# power_board.net
KiCad netlist of a schematic drawn in EAGLE
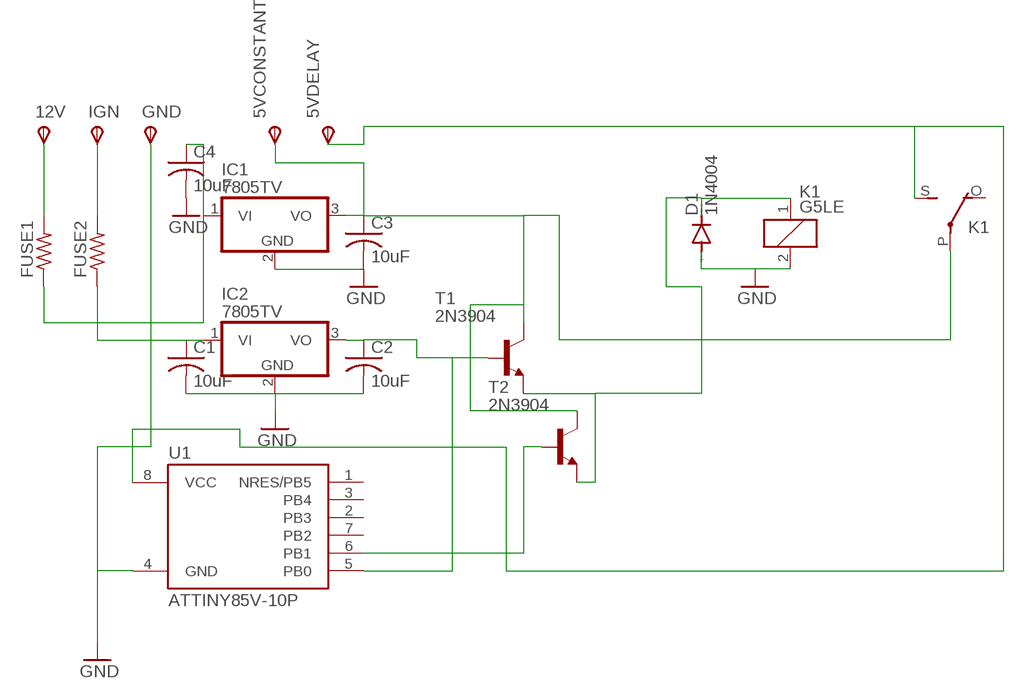
[diagram p0: schematic, sheet 1]

(export (version "E")
  (design (tool "Eeschema 10.0.6"))
  (components
    (comp (ref "5VCONSTANT")
      (value "TPSPAD1-13Y")
      (footprint "eagle-import:P1-13Y")
      (libsource (lib "eagle-import") (part "TPSPAD1-13Y"))
    )
    (comp (ref "5VDELAY")
      (value "TPSPAD1-13Y")
      (footprint "eagle-import:P1-13Y")
      (libsource (lib "eagle-import") (part "TPSPAD1-13Y"))
    )
    (comp (ref "12V")
      (value "TPSPAD1-13Y")
      (footprint "eagle-import:P1-13Y")
      (libsource (lib "eagle-import") (part "TPSPAD1-13Y"))
    )
    (comp (ref "C1")
      (value "10uF")
      (footprint "eagle-import:C0603")
      (libsource (lib "eagle-import") (part "C-USC0603"))
    )
    (comp (ref "C2")
      (value "10uF")
      (footprint "eagle-import:C0603")
      (libsource (lib "eagle-import") (part "C-USC0603"))
    )
    (comp (ref "C3")
      (value "10uF")
      (footprint "eagle-import:C0603")
      (libsource (lib "eagle-import") (part "C-USC0603"))
    )
    (comp (ref "C4")
      (value "10uF")
      (footprint "eagle-import:C0603")
      (libsource (lib "eagle-import") (part "C-USC0603"))
    )
    (comp (ref "D1")
      (value "1N4004")
      (footprint "eagle-import:DO41-10")
      (libsource (lib "eagle-import") (part "1N4004"))
    )
    (comp (ref "FUSE1")
      (value "R-US_R0805")
      (footprint "eagle-import:R0805")
      (libsource (lib "eagle-import") (part "R-US_R0805"))
    )
    (comp (ref "FUSE2")
      (value "R-US_R0805")
      (footprint "eagle-import:R0805")
      (libsource (lib "eagle-import") (part "R-US_R0805"))
    )
    (comp (ref "GND")
      (value "TPSPAD1-13Y")
      (footprint "eagle-import:P1-13Y")
      (libsource (lib "eagle-import") (part "TPSPAD1-13Y"))
    )
    (comp (ref "IC1")
      (value "7805TV")
      (footprint "eagle-import:TO220V")
      (libsource (lib "eagle-import") (part "78TV05"))
    )
    (comp (ref "IC2")
      (value "7805TV")
      (footprint "eagle-import:TO220V")
      (libsource (lib "eagle-import") (part "78TV05"))
    )
    (comp (ref "IGN")
      (value "TPSPAD1-13Y")
      (footprint "eagle-import:P1-13Y")
      (libsource (lib "eagle-import") (part "TPSPAD1-13Y"))
    )
    (comp (ref "K1")
      (value "G5LE")
      (footprint "eagle-import:G5LE")
      (libsource (lib "eagle-import") (part "G5LE"))
    )
    (comp (ref "T1")
      (value "2N3904")
      (footprint "eagle-import:TO92")
      (libsource (lib "eagle-import") (part "2N3904"))
    )
    (comp (ref "T2")
      (value "2N3904")
      (footprint "eagle-import:TO92")
      (libsource (lib "eagle-import") (part "2N3904"))
    )
    (comp (ref "U1")
      (value "ATTINY85V-10P")
      (footprint "eagle-import:PDIP08_300MIL")
      (libsource (lib "eagle-import") (part "ATTINY85PV-10"))
    )
  )
  (nets
    (net (code "1") (name "GND") (class "Default")
      (node (ref "C1") (pin "2") (pinfunction "2_2") (pintype "passive"))
      (node (ref "C2") (pin "2") (pinfunction "2_2") (pintype "passive"))
      (node (ref "C3") (pin "2") (pinfunction "2_2") (pintype "passive"))
      (node (ref "C4") (pin "2") (pinfunction "2_2") (pintype "passive"))
      (node (ref "D1") (pin "A") (pinfunction "A_A") (pintype "passive"))
      (node (ref "GND") (pin "TP") (pinfunction "PP_TP") (pintype "input"))
      (node (ref "IC1") (pin "2") (pinfunction "GND_2") (pintype "passive"))
      (node (ref "IC2") (pin "2") (pinfunction "GND_2") (pintype "passive"))
      (node (ref "K1") (pin "2") (pinfunction "2_2") (pintype "passive"))
      (node (ref "U1") (pin "4") (pinfunction "GND_4") (pintype "power_in"))
    )
    (net (code "2") (name "Net-(5VCONSTANT-PP)") (class "Default")
      (node (ref "5VCONSTANT") (pin "TP") (pinfunction "PP_TP") (pintype "input"))
      (node (ref "C3") (pin "1") (pinfunction "1_1") (pintype "passive"))
      (node (ref "IC1") (pin "3") (pinfunction "VO_3") (pintype "passive"))
      (node (ref "K1") (pin "P") (pinfunction "P_P") (pintype "passive"))
      (node (ref "T1") (pin "1") (pinfunction "C_1") (pintype "passive"))
      (node (ref "T2") (pin "1") (pinfunction "C_1") (pintype "passive"))
    )
    (net (code "3") (name "Net-(5VDELAY-PP)") (class "Default")
      (node (ref "5VDELAY") (pin "TP") (pinfunction "PP_TP") (pintype "input"))
      (node (ref "K1") (pin "S") (pinfunction "S_S") (pintype "passive"))
      (node (ref "U1") (pin "8") (pinfunction "VCC_8") (pintype "power_in"))
    )
    (net (code "4") (name "Net-(12V-PP)") (class "Default")
      (node (ref "12V") (pin "TP") (pinfunction "PP_TP") (pintype "input"))
      (node (ref "FUSE1") (pin "2") (pinfunction "2_2") (pintype "passive"))
    )
    (net (code "5") (name "Net-(IC1-VI)") (class "Default")
      (node (ref "C4") (pin "1") (pinfunction "1_1") (pintype "passive"))
      (node (ref "FUSE1") (pin "1") (pinfunction "1_1") (pintype "passive"))
      (node (ref "IC1") (pin "1") (pinfunction "VI_1") (pintype "input"))
    )
    (net (code "6") (name "Net-(IC2-VI)") (class "Default")
      (node (ref "C1") (pin "1") (pinfunction "1_1") (pintype "passive"))
      (node (ref "FUSE2") (pin "1") (pinfunction "1_1") (pintype "passive"))
      (node (ref "IC2") (pin "1") (pinfunction "VI_1") (pintype "input"))
    )
    (net (code "7") (name "Net-(IC2-VO)") (class "Default")
      (node (ref "C2") (pin "1") (pinfunction "1_1") (pintype "passive"))
      (node (ref "IC2") (pin "3") (pinfunction "VO_3") (pintype "passive"))
      (node (ref "T1") (pin "2") (pinfunction "B_2") (pintype "passive"))
      (node (ref "U1") (pin "5") (pinfunction "PB0_5") (pintype "bidirectional"))
    )
    (net (code "8") (name "Net-(IGN-PP)") (class "Default")
      (node (ref "FUSE2") (pin "2") (pinfunction "2_2") (pintype "passive"))
      (node (ref "IGN") (pin "TP") (pinfunction "PP_TP") (pintype "input"))
    )
    (net (code "9") (name "Net-(T1-E)") (class "Default")
      (node (ref "D1") (pin "C") (pinfunction "C_C") (pintype "passive"))
      (node (ref "K1") (pin "1") (pinfunction "1_1") (pintype "passive"))
      (node (ref "T1") (pin "3") (pinfunction "E_3") (pintype "passive"))
      (node (ref "T2") (pin "3") (pinfunction "E_3") (pintype "passive"))
    )
    (net (code "10") (name "Net-(T2-B)") (class "Default")
      (node (ref "T2") (pin "2") (pinfunction "B_2") (pintype "passive"))
      (node (ref "U1") (pin "6") (pinfunction "PB1_6") (pintype "bidirectional"))
    )
    (net (code "11") (name "unconnected-(K1-PadO)") (class "Default")
      (node (ref "K1") (pin "O") (pinfunction "O_O") (pintype "passive"))
    )
    (net (code "12") (name "unconnected-(U1-NRES{slash}PB5-Pad1)") (class "Default")
      (node (ref "U1") (pin "1") (pinfunction "NRES/PB5_1") (pintype "bidirectional"))
    )
    (net (code "13") (name "unconnected-(U1-PB2-Pad7)") (class "Default")
      (node (ref "U1") (pin "7") (pinfunction "PB2_7") (pintype "bidirectional"))
    )
    (net (code "14") (name "unconnected-(U1-PB3-Pad2)") (class "Default")
      (node (ref "U1") (pin "2") (pinfunction "PB3_2") (pintype "bidirectional"))
    )
    (net (code "15") (name "unconnected-(U1-PB4-Pad3)") (class "Default")
      (node (ref "U1") (pin "3") (pinfunction "PB4_3") (pintype "bidirectional"))
    )
  )
)
